# WifiWeatherGuy.net
KiCad netlist of a schematic drawn in EAGLE
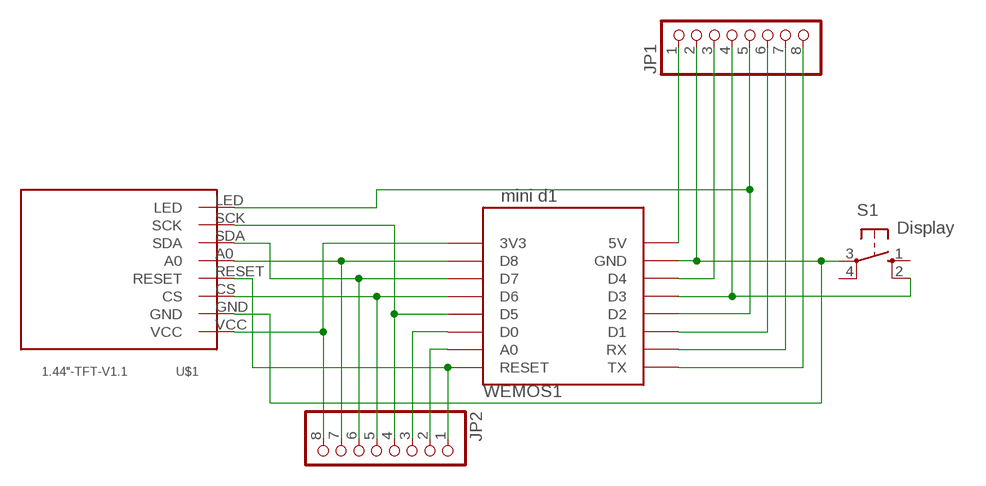
[diagram p0: schematic, sheet 1]

(export (version "E")
  (design (tool "Eeschema 10.0.6"))
  (components
    (comp (ref "JP1")
      (value "PINHD-1X8")
      (footprint "eagle-import:1X08")
      (libsource (lib "eagle-import") (part "PINHD-1X8"))
    )
    (comp (ref "JP2")
      (value "PINHD-1X8")
      (footprint "eagle-import:1X08")
      (libsource (lib "eagle-import") (part "PINHD-1X8"))
    )
    (comp (ref "S1")
      (value "Display")
      (footprint "eagle-import:B3F-10XX")
      (fields (field (name "MPN") "B3F-1000"))
      (libsource (lib "eagle-import") (part "10-XX"))
    )
    (comp (ref "U$1")
      (value "1.44\"-TFT-V1.1")
      (footprint "eagle-import:1.44-TFT-V1.1")
      (libsource (lib "eagle-import") (part "1.44{dblquote}-TFT-V1.1"))
    )
    (comp (ref "WEMOS1")
      (value "mini d1")
      (footprint "eagle-import:WEMOS-D1-MINI")
      (libsource (lib "eagle-import") (part "WEMOS-D1-MINI"))
    )
  )
  (nets
    (net (code "1") (name "Net-(JP1-Pad1)") (class "Default")
      (node (ref "JP1") (pin "1") (pinfunction "1_1") (pintype "passive"))
      (node (ref "WEMOS1") (pin "5V") (pinfunction "5V_5V") (pintype "bidirectional"))
    )
    (net (code "2") (name "Net-(JP1-Pad3)") (class "Default")
      (node (ref "JP1") (pin "3") (pinfunction "3_3") (pintype "passive"))
      (node (ref "WEMOS1") (pin "D4") (pinfunction "D4_D4") (pintype "bidirectional"))
    )
    (net (code "3") (name "Net-(JP1-Pad5)") (class "Default")
      (node (ref "JP1") (pin "5") (pinfunction "5_5") (pintype "passive"))
      (node (ref "U$1") (pin "LED") (pinfunction "LED_LED") (pintype "bidirectional"))
      (node (ref "WEMOS1") (pin "D2") (pinfunction "D2_D2") (pintype "bidirectional"))
    )
    (net (code "4") (name "Net-(JP1-Pad6)") (class "Default")
      (node (ref "JP1") (pin "6") (pinfunction "6_6") (pintype "passive"))
      (node (ref "WEMOS1") (pin "D1") (pinfunction "D1_D1") (pintype "bidirectional"))
    )
    (net (code "5") (name "Net-(JP1-Pad7)") (class "Default")
      (node (ref "JP1") (pin "7") (pinfunction "7_7") (pintype "passive"))
      (node (ref "WEMOS1") (pin "RX") (pinfunction "RX_RX") (pintype "bidirectional"))
    )
    (net (code "6") (name "Net-(JP1-Pad8)") (class "Default")
      (node (ref "JP1") (pin "8") (pinfunction "8_8") (pintype "passive"))
      (node (ref "WEMOS1") (pin "TX") (pinfunction "TX_TX") (pintype "bidirectional"))
    )
    (net (code "7") (name "Net-(JP2-Pad1)") (class "Default")
      (node (ref "JP2") (pin "1") (pinfunction "1_1") (pintype "passive"))
      (node (ref "U$1") (pin "RESET") (pinfunction "RESET_RESET") (pintype "bidirectional"))
      (node (ref "WEMOS1") (pin "RESET") (pinfunction "RESET_RESET") (pintype "bidirectional"))
    )
    (net (code "8") (name "Net-(JP2-Pad2)") (class "Default")
      (node (ref "JP2") (pin "2") (pinfunction "2_2") (pintype "passive"))
      (node (ref "WEMOS1") (pin "A0") (pinfunction "A0_A0") (pintype "bidirectional"))
    )
    (net (code "9") (name "Net-(JP2-Pad3)") (class "Default")
      (node (ref "JP2") (pin "3") (pinfunction "3_3") (pintype "passive"))
      (node (ref "WEMOS1") (pin "D0") (pinfunction "D0_D0") (pintype "bidirectional"))
    )
    (net (code "10") (name "Net-(JP2-Pad4)") (class "Default")
      (node (ref "JP2") (pin "4") (pinfunction "4_4") (pintype "passive"))
      (node (ref "U$1") (pin "SCK") (pinfunction "SCK_SCK") (pintype "bidirectional"))
      (node (ref "WEMOS1") (pin "D5") (pinfunction "D5_D5") (pintype "bidirectional"))
    )
    (net (code "11") (name "Net-(JP2-Pad5)") (class "Default")
      (node (ref "JP2") (pin "5") (pinfunction "5_5") (pintype "passive"))
      (node (ref "U$1") (pin "CS") (pinfunction "CS_CS") (pintype "bidirectional"))
      (node (ref "WEMOS1") (pin "D6") (pinfunction "D6_D6") (pintype "bidirectional"))
    )
    (net (code "12") (name "Net-(JP2-Pad6)") (class "Default")
      (node (ref "JP2") (pin "6") (pinfunction "6_6") (pintype "passive"))
      (node (ref "U$1") (pin "SDA") (pinfunction "SDA_SDA") (pintype "bidirectional"))
      (node (ref "WEMOS1") (pin "D7") (pinfunction "D7_D7") (pintype "bidirectional"))
    )
    (net (code "13") (name "Net-(JP2-Pad7)") (class "Default")
      (node (ref "JP2") (pin "7") (pinfunction "7_7") (pintype "passive"))
      (node (ref "U$1") (pin "A0") (pinfunction "A0_A0") (pintype "bidirectional"))
      (node (ref "WEMOS1") (pin "D8") (pinfunction "D8_D8") (pintype "bidirectional"))
    )
    (net (code "14") (name "Net-(JP2-Pad8)") (class "Default")
      (node (ref "JP2") (pin "8") (pinfunction "8_8") (pintype "passive"))
      (node (ref "U$1") (pin "VCC") (pinfunction "VCC_VCC") (pintype "bidirectional"))
      (node (ref "WEMOS1") (pin "3V3") (pinfunction "3V3_3V3") (pintype "bidirectional"))
    )
    (net (code "15") (name "Net-(S1-P)") (class "Default")
      (node (ref "JP1") (pin "2") (pinfunction "2_2") (pintype "passive"))
      (node (ref "S1") (pin "3") (pinfunction "P_3") (pintype "passive"))
      (node (ref "U$1") (pin "GND") (pinfunction "GND_GND") (pintype "bidirectional"))
      (node (ref "WEMOS1") (pin "GND") (pinfunction "GND_GND") (pintype "bidirectional"))
    )
    (net (code "16") (name "Net-(S1-S1)") (class "Default")
      (node (ref "JP1") (pin "4") (pinfunction "4_4") (pintype "passive"))
      (node (ref "S1") (pin "2") (pinfunction "S1_2") (pintype "passive"))
      (node (ref "WEMOS1") (pin "D3") (pinfunction "D3_D3") (pintype "bidirectional"))
    )
    (net (code "17") (name "unconnected-(S1-P1-Pad4)") (class "Default")
      (node (ref "S1") (pin "4") (pinfunction "P1_4") (pintype "passive"))
    )
    (net (code "18") (name "unconnected-(S1-S-Pad1)") (class "Default")
      (node (ref "S1") (pin "1") (pinfunction "S_1") (pintype "passive"))
    )
  )
)
